# c64saver_1_3.net
KiCad netlist of a schematic drawn in EAGLE
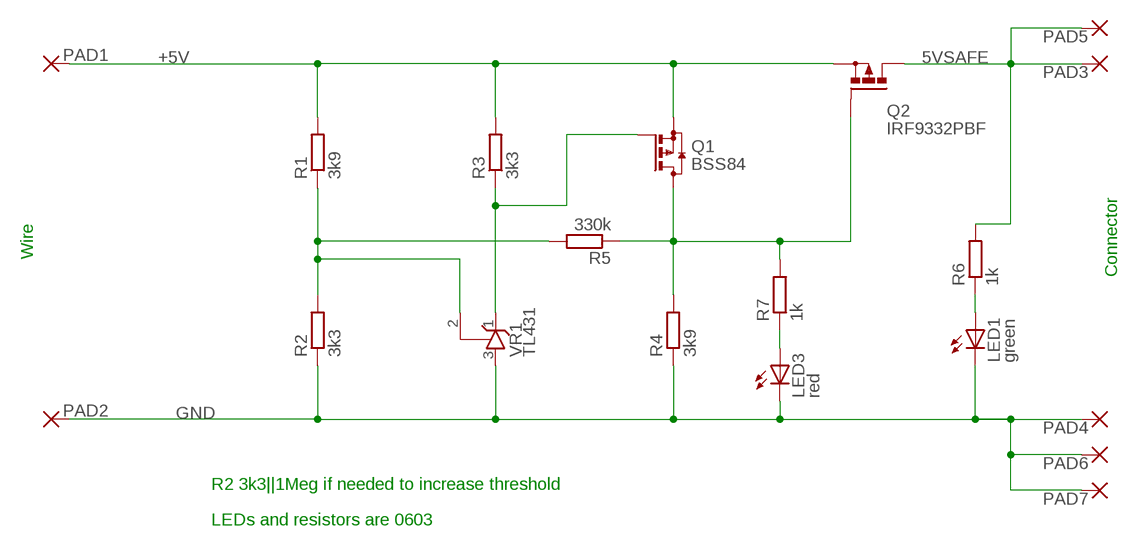
[diagram p0: schematic, sheet 1]

(export (version "E")
  (design (tool "Eeschema 10.0.6"))
  (components
    (comp (ref "LED1")
      (value "green")
      (footprint "eagle-import:CHIPLED_0603")
      (libsource (lib "eagle-import") (part "LEDCHIPLED_0603"))
    )
    (comp (ref "LED3")
      (value "red")
      (footprint "eagle-import:CHIPLED_0603")
      (libsource (lib "eagle-import") (part "LEDCHIPLED_0603"))
    )
    (comp (ref "PAD1")
      (value "WIREPADSMD1,27-254")
      (footprint "eagle-import:SMD1,27-2,54")
      (libsource (lib "eagle-import") (part "WIREPADSMD1,27-254"))
    )
    (comp (ref "PAD2")
      (value "WIREPADSMD1,27-254")
      (footprint "eagle-import:SMD1,27-2,54")
      (libsource (lib "eagle-import") (part "WIREPADSMD1,27-254"))
    )
    (comp (ref "PAD3")
      (value "WIREPADSMD2,54-2,54")
      (footprint "eagle-import:SMD2,54-2,54")
      (libsource (lib "eagle-import") (part "WIREPADSMD2,54-2,54"))
    )
    (comp (ref "PAD4")
      (value "WIREPADSMD1,27-254")
      (footprint "eagle-import:SMD1,27-2,54")
      (libsource (lib "eagle-import") (part "WIREPADSMD1,27-254"))
    )
    (comp (ref "PAD5")
      (value "WIREPADSMD2,54-2,54")
      (footprint "eagle-import:SMD2,54-2,54")
      (libsource (lib "eagle-import") (part "WIREPADSMD2,54-2,54"))
    )
    (comp (ref "PAD6")
      (value "WIREPADSMD1,27-254")
      (footprint "eagle-import:SMD1,27-2,54")
      (libsource (lib "eagle-import") (part "WIREPADSMD1,27-254"))
    )
    (comp (ref "PAD7")
      (value "WIREPADSMD1,27-254")
      (footprint "eagle-import:SMD1,27-2,54")
      (libsource (lib "eagle-import") (part "WIREPADSMD1,27-254"))
    )
    (comp (ref "Q1")
      (value "BSS84")
      (footprint "eagle-import:SOT23")
      (libsource (lib "eagle-import") (part "BSS84"))
    )
    (comp (ref "Q2")
      (value "IRF9332PBF")
      (footprint "eagle-import:SO-08")
      (libsource (lib "eagle-import") (part "P-MOSFET-SO8"))
    )
    (comp (ref "R1")
      (value "3k9")
      (footprint "eagle-import:R0603")
      (libsource (lib "eagle-import") (part "R-EU_R0603"))
    )
    (comp (ref "R2")
      (value "3k3")
      (footprint "eagle-import:R0603")
      (libsource (lib "eagle-import") (part "R-EU_R0603"))
    )
    (comp (ref "R3")
      (value "3k3")
      (footprint "eagle-import:R0603")
      (libsource (lib "eagle-import") (part "R-EU_R0603"))
    )
    (comp (ref "R4")
      (value "3k9")
      (footprint "eagle-import:R0603")
      (libsource (lib "eagle-import") (part "R-EU_R0603"))
    )
    (comp (ref "R5")
      (value "330k")
      (footprint "eagle-import:R0603")
      (libsource (lib "eagle-import") (part "R-EU_R0603"))
    )
    (comp (ref "R6")
      (value "1k")
      (footprint "eagle-import:R0603")
      (libsource (lib "eagle-import") (part "R-EU_R0603"))
    )
    (comp (ref "R7")
      (value "1k")
      (footprint "eagle-import:R0603")
      (libsource (lib "eagle-import") (part "R-EU_R0603"))
    )
    (comp (ref "VR1")
      (value "TL431")
      (footprint "eagle-import:SOT23")
      (libsource (lib "eagle-import") (part "TL431CLPSOT23"))
    )
  )
  (nets
    (net (code "1") (name "/+5V") (class "Default")
      (node (ref "PAD1") (pin "1") (pinfunction "P_1") (pintype "passive"))
      (node (ref "Q1") (pin "2") (pinfunction "S_2") (pintype "passive"))
      (node (ref "Q2") (pin "1") (pinfunction "S_1") (pintype "passive"))
      (node (ref "Q2") (pin "2") (pinfunction "S_2") (pintype "passive"))
      (node (ref "Q2") (pin "3") (pinfunction "S_3") (pintype "passive"))
      (node (ref "R1") (pin "2") (pinfunction "2_2") (pintype "passive"))
      (node (ref "R3") (pin "2") (pinfunction "2_2") (pintype "passive"))
    )
    (net (code "2") (name "/5VSAFE") (class "Default")
      (node (ref "PAD3") (pin "1") (pinfunction "P_1") (pintype "passive"))
      (node (ref "PAD5") (pin "1") (pinfunction "P_1") (pintype "passive"))
      (node (ref "Q2") (pin "5") (pinfunction "D_5") (pintype "passive"))
      (node (ref "Q2") (pin "6") (pinfunction "D_6") (pintype "passive"))
      (node (ref "Q2") (pin "7") (pinfunction "D_7") (pintype "passive"))
      (node (ref "Q2") (pin "8") (pinfunction "D_8") (pintype "passive"))
      (node (ref "R6") (pin "2") (pinfunction "2_2") (pintype "passive"))
    )
    (net (code "3") (name "/GND") (class "Default")
      (node (ref "LED1") (pin "C") (pinfunction "C_C") (pintype "passive"))
      (node (ref "LED3") (pin "C") (pinfunction "C_C") (pintype "passive"))
      (node (ref "PAD2") (pin "1") (pinfunction "P_1") (pintype "passive"))
      (node (ref "PAD4") (pin "1") (pinfunction "P_1") (pintype "passive"))
      (node (ref "PAD6") (pin "1") (pinfunction "P_1") (pintype "passive"))
      (node (ref "PAD7") (pin "1") (pinfunction "P_1") (pintype "passive"))
      (node (ref "R2") (pin "1") (pinfunction "1_1") (pintype "passive"))
      (node (ref "R4") (pin "1") (pinfunction "1_1") (pintype "passive"))
      (node (ref "VR1") (pin "3") (pinfunction "A_3") (pintype "passive"))
    )
    (net (code "4") (name "Net-(LED1-PadA)") (class "Default")
      (node (ref "LED1") (pin "A") (pinfunction "A_A") (pintype "passive"))
      (node (ref "R6") (pin "1") (pinfunction "1_1") (pintype "passive"))
    )
    (net (code "5") (name "Net-(LED3-PadA)") (class "Default")
      (node (ref "LED3") (pin "A") (pinfunction "A_A") (pintype "passive"))
      (node (ref "R7") (pin "1") (pinfunction "1_1") (pintype "passive"))
    )
    (net (code "6") (name "Net-(Q1-D)") (class "Default")
      (node (ref "Q1") (pin "3") (pinfunction "D_3") (pintype "passive"))
      (node (ref "Q2") (pin "4") (pinfunction "G_4") (pintype "passive"))
      (node (ref "R4") (pin "2") (pinfunction "2_2") (pintype "passive"))
      (node (ref "R5") (pin "1") (pinfunction "1_1") (pintype "passive"))
      (node (ref "R7") (pin "2") (pinfunction "2_2") (pintype "passive"))
    )
    (net (code "7") (name "Net-(Q1-G)") (class "Default")
      (node (ref "Q1") (pin "1") (pinfunction "G_1") (pintype "passive"))
      (node (ref "R3") (pin "1") (pinfunction "1_1") (pintype "passive"))
      (node (ref "VR1") (pin "1") (pinfunction "C_1") (pintype "passive"))
    )
    (net (code "8") (name "Net-(VR1-R)") (class "Default")
      (node (ref "R1") (pin "1") (pinfunction "1_1") (pintype "passive"))
      (node (ref "R2") (pin "2") (pinfunction "2_2") (pintype "passive"))
      (node (ref "R5") (pin "2") (pinfunction "2_2") (pintype "passive"))
      (node (ref "VR1") (pin "2") (pinfunction "R_2") (pintype "passive"))
    )
  )
)
